# power.net
KiCad netlist of a schematic drawn in EAGLE
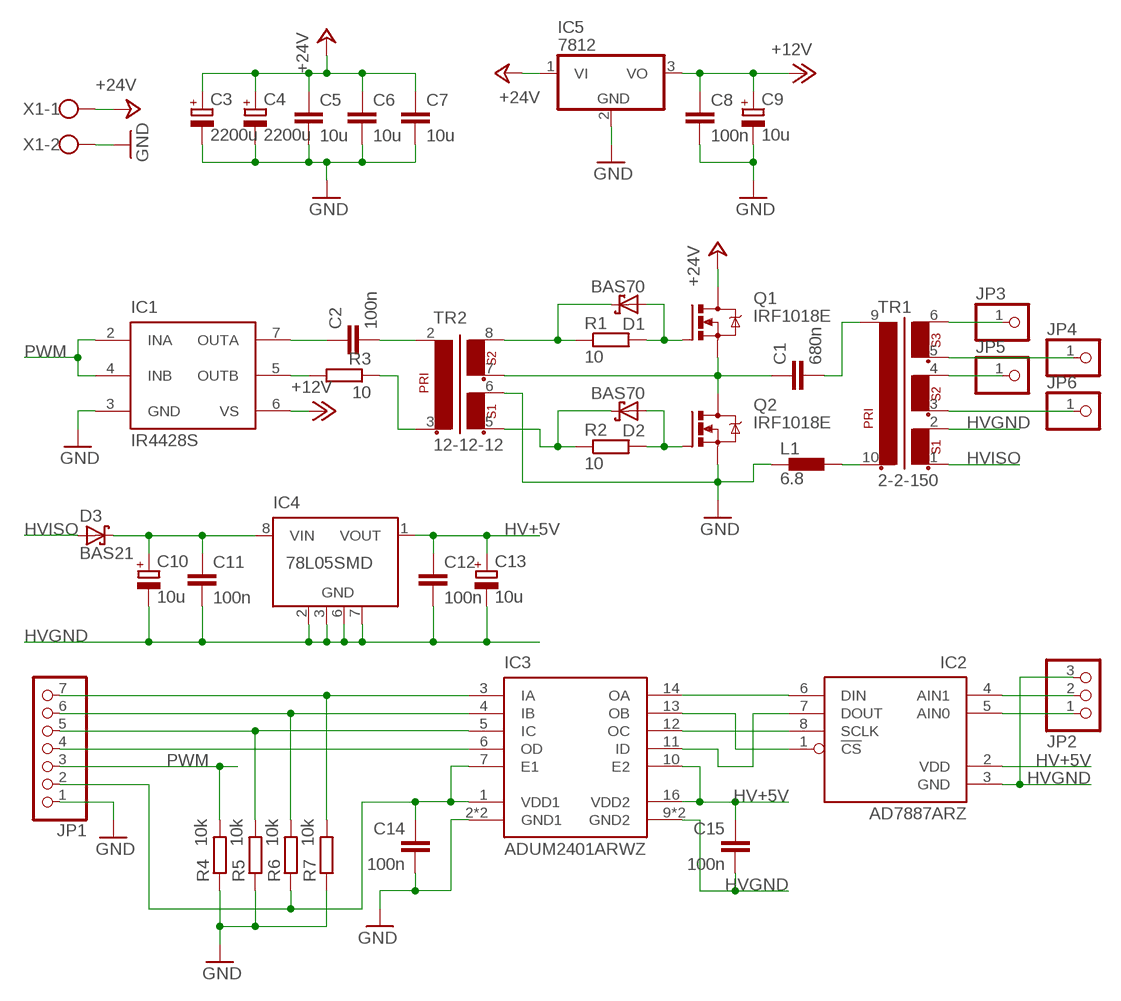
[diagram p0: schematic, sheet 1]

(export (version "E")
  (design (tool "Eeschema 10.0.6"))
  (components
    (comp (ref "C1")
      (value "680n")
      (footprint "eagle-import:C150-084X183")
      (libsource (lib "eagle-import") (part "C-EU150-084X183"))
    )
    (comp (ref "C2")
      (value "100n")
      (footprint "eagle-import:C1206")
      (libsource (lib "eagle-import") (part "C-EUC1206"))
    )
    (comp (ref "C3")
      (value "2200u")
      (footprint "eagle-import:E7,5-16")
      (libsource (lib "eagle-import") (part "CPOL-EUE7.5-16"))
    )
    (comp (ref "C4")
      (value "2200u")
      (footprint "eagle-import:E7,5-16")
      (libsource (lib "eagle-import") (part "CPOL-EUE7.5-16"))
    )
    (comp (ref "C5")
      (value "10u")
      (footprint "eagle-import:C1210")
      (libsource (lib "eagle-import") (part "C-EUC1210"))
    )
    (comp (ref "C6")
      (value "10u")
      (footprint "eagle-import:C1210")
      (libsource (lib "eagle-import") (part "C-EUC1210"))
    )
    (comp (ref "C7")
      (value "10u")
      (footprint "eagle-import:C1210")
      (libsource (lib "eagle-import") (part "C-EUC1210"))
    )
    (comp (ref "C8")
      (value "100n")
      (footprint "eagle-import:C1206")
      (libsource (lib "eagle-import") (part "C-EUC1206"))
    )
    (comp (ref "C9")
      (value "10u")
      (footprint "eagle-import:B_3528-21R")
      (libsource (lib "eagle-import") (part "CPOL-EUB/3528-21R"))
    )
    (comp (ref "C10")
      (value "10u")
      (footprint "eagle-import:B_3528-21R")
      (libsource (lib "eagle-import") (part "CPOL-EUB/3528-21R"))
    )
    (comp (ref "C11")
      (value "100n")
      (footprint "eagle-import:C1206")
      (libsource (lib "eagle-import") (part "C-EUC1206"))
    )
    (comp (ref "C12")
      (value "100n")
      (footprint "eagle-import:C1206")
      (libsource (lib "eagle-import") (part "C-EUC1206"))
    )
    (comp (ref "C13")
      (value "10u")
      (footprint "eagle-import:B_3528-21R")
      (libsource (lib "eagle-import") (part "CPOL-EUB/3528-21R"))
    )
    (comp (ref "C14")
      (value "100n")
      (footprint "eagle-import:C1206")
      (libsource (lib "eagle-import") (part "C-EUC1206"))
    )
    (comp (ref "C15")
      (value "100n")
      (footprint "eagle-import:C1206")
      (libsource (lib "eagle-import") (part "C-EUC1206"))
    )
    (comp (ref "D1")
      (value "BAS70")
      (footprint "eagle-import:SOT23")
      (libsource (lib "eagle-import") (part "BAS70"))
    )
    (comp (ref "D2")
      (value "BAS70")
      (footprint "eagle-import:SOT23")
      (libsource (lib "eagle-import") (part "BAS70"))
    )
    (comp (ref "D3")
      (value "BAS21")
      (footprint "eagle-import:SOT23")
      (libsource (lib "eagle-import") (part "BAS70"))
    )
    (comp (ref "IC1")
      (value "IR4428S")
      (footprint "eagle-import:SO08")
      (libsource (lib "eagle-import") (part "IR442S8"))
    )
    (comp (ref "IC2")
      (value "AD7887ARZ")
      (footprint "eagle-import:SO08")
      (libsource (lib "eagle-import") (part "AD7887ARZ"))
    )
    (comp (ref "IC3")
      (value "ADUM2401ARWZ")
      (footprint "eagle-import:SO-16W")
      (libsource (lib "eagle-import") (part "ADUM2401RWZA"))
    )
    (comp (ref "IC4")
      (value "78L05SMD")
      (footprint "eagle-import:SO08")
      (libsource (lib "eagle-import") (part "78LSMD05"))
    )
    (comp (ref "IC5")
      (value "7812")
      (footprint "eagle-import:D2PACK")
      (libsource (lib "eagle-import") (part "7812"))
    )
    (comp (ref "JP1")
      (value "PINHD-1X7/90")
      (footprint "eagle-import:1X07_90")
      (libsource (lib "eagle-import") (part "PINHD-1X7/90"))
    )
    (comp (ref "JP2")
      (value "PINHD-1X3/90")
      (footprint "eagle-import:1X03_90")
      (libsource (lib "eagle-import") (part "PINHD-1X3/90"))
    )
    (comp (ref "JP3")
      (value "PINHD-1X1")
      (footprint "eagle-import:1X01")
      (libsource (lib "eagle-import") (part "PINHD-1X1"))
    )
    (comp (ref "JP4")
      (value "PINHD-1X1")
      (footprint "eagle-import:1X01")
      (libsource (lib "eagle-import") (part "PINHD-1X1"))
    )
    (comp (ref "JP5")
      (value "PINHD-1X1")
      (footprint "eagle-import:1X01")
      (libsource (lib "eagle-import") (part "PINHD-1X1"))
    )
    (comp (ref "JP6")
      (value "PINHD-1X1")
      (footprint "eagle-import:1X01")
      (libsource (lib "eagle-import") (part "PINHD-1X1"))
    )
    (comp (ref "L1")
      (value "6.8")
      (footprint "eagle-import:TSL1112")
      (libsource (lib "eagle-import") (part "TSL1112"))
    )
    (comp (ref "Q1")
      (value "IRF1018E")
      (footprint "eagle-import:TO220BV")
      (libsource (lib "eagle-import") (part "IRF1018E"))
    )
    (comp (ref "Q2")
      (value "IRF1018E")
      (footprint "eagle-import:TO220BV")
      (libsource (lib "eagle-import") (part "IRF1018E"))
    )
    (comp (ref "R1")
      (value "10")
      (footprint "eagle-import:R0805")
      (libsource (lib "eagle-import") (part "R-EU_R0805"))
    )
    (comp (ref "R2")
      (value "10")
      (footprint "eagle-import:R0805")
      (libsource (lib "eagle-import") (part "R-EU_R0805"))
    )
    (comp (ref "R3")
      (value "10")
      (footprint "eagle-import:R0805")
      (libsource (lib "eagle-import") (part "R-EU_R0805"))
    )
    (comp (ref "R4")
      (value "10k")
      (footprint "eagle-import:R0805")
      (libsource (lib "eagle-import") (part "R-EU_R0805"))
    )
    (comp (ref "R5")
      (value "10k")
      (footprint "eagle-import:R0805")
      (libsource (lib "eagle-import") (part "R-EU_R0805"))
    )
    (comp (ref "R6")
      (value "10k")
      (footprint "eagle-import:R0805")
      (libsource (lib "eagle-import") (part "R-EU_R0805"))
    )
    (comp (ref "R7")
      (value "10k")
      (footprint "eagle-import:R0805")
      (libsource (lib "eagle-import") (part "R-EU_R0805"))
    )
    (comp (ref "TR1")
      (value "2-2-150")
      (footprint "eagle-import:RM12T1")
      (libsource (lib "eagle-import") (part "2-2-150"))
    )
    (comp (ref "TR2")
      (value "12-12-12")
      (footprint "eagle-import:RM5LS")
      (libsource (lib "eagle-import") (part "12-12-12"))
    )
    (comp (ref "X1")
      (value "W237-102")
      (footprint "eagle-import:W237-102")
      (fields (field (name "MPN") "237-102"))
      (libsource (lib "eagle-import") (part "W237-102"))
    )
  )
  (nets
    (net (code "1") (name "+12V") (class "Default")
      (node (ref "C8") (pin "1") (pinfunction "1_1") (pintype "passive"))
      (node (ref "C9") (pin "+") (pinfunction "+_+") (pintype "passive"))
      (node (ref "IC1") (pin "6") (pinfunction "VS_6") (pintype "power_in"))
      (node (ref "IC5") (pin "3") (pinfunction "VO_3") (pintype "passive"))
    )
    (net (code "2") (name "+24V") (class "Default")
      (node (ref "C3") (pin "+") (pinfunction "+_+") (pintype "passive"))
      (node (ref "C4") (pin "+") (pinfunction "+_+") (pintype "passive"))
      (node (ref "C5") (pin "1") (pinfunction "1_1") (pintype "passive"))
      (node (ref "C6") (pin "1") (pinfunction "1_1") (pintype "passive"))
      (node (ref "C7") (pin "1") (pinfunction "1_1") (pintype "passive"))
      (node (ref "IC5") (pin "1") (pinfunction "VI_1") (pintype "input"))
      (node (ref "Q1") (pin "D") (pinfunction "D_D") (pintype "passive"))
      (node (ref "X1") (pin "1") (pinfunction "KL_1") (pintype "passive"))
    )
    (net (code "3") (name "/HV+5V") (class "Default")
      (node (ref "C12") (pin "1") (pinfunction "1_1") (pintype "passive"))
      (node (ref "C13") (pin "+") (pinfunction "+_+") (pintype "passive"))
      (node (ref "C15") (pin "1") (pinfunction "1_1") (pintype "passive"))
      (node (ref "IC2") (pin "2") (pinfunction "VDD_2") (pintype "power_in"))
      (node (ref "IC3") (pin "10") (pinfunction "E2_10") (pintype "input"))
      (node (ref "IC3") (pin "16") (pinfunction "VDD2_16") (pintype "power_in"))
      (node (ref "IC4") (pin "1") (pinfunction "VOUT_1") (pintype "output"))
    )
    (net (code "4") (name "/HVGND") (class "Default")
      (node (ref "C10") (pin "-") (pinfunction "-_-") (pintype "passive"))
      (node (ref "C11") (pin "2") (pinfunction "2_2") (pintype "passive"))
      (node (ref "C12") (pin "2") (pinfunction "2_2") (pintype "passive"))
      (node (ref "C13") (pin "-") (pinfunction "-_-") (pintype "passive"))
      (node (ref "C15") (pin "2") (pinfunction "2_2") (pintype "passive"))
      (node (ref "IC2") (pin "3") (pinfunction "GND_3") (pintype "power_in"))
      (node (ref "IC3") (pin "15") (pinfunction "GND2_15") (pintype "power_in"))
      (node (ref "IC3") (pin "9") (pinfunction "GND2_9") (pintype "power_in"))
      (node (ref "IC4") (pin "2") (pinfunction "GND_2") (pintype "power_in"))
      (node (ref "IC4") (pin "3") (pinfunction "GND_3") (pintype "power_in"))
      (node (ref "IC4") (pin "6") (pinfunction "GND_6") (pintype "power_in"))
      (node (ref "IC4") (pin "7") (pinfunction "GND_7") (pintype "power_in"))
      (node (ref "JP2") (pin "3") (pinfunction "3_3") (pintype "passive"))
      (node (ref "TR1") (pin "2") (pinfunction "4_2") (pintype "passive"))
    )
    (net (code "5") (name "/HVISO") (class "Default")
      (node (ref "D3") (pin "1") (pinfunction "A_1") (pintype "passive"))
      (node (ref "TR1") (pin "1") (pinfunction "3_1") (pintype "passive"))
    )
    (net (code "6") (name "/PWM") (class "Default")
      (node (ref "IC1") (pin "2") (pinfunction "INA_2") (pintype "input"))
      (node (ref "IC1") (pin "4") (pinfunction "INB_4") (pintype "input"))
      (node (ref "JP1") (pin "3") (pinfunction "3_3") (pintype "passive"))
      (node (ref "R4") (pin "2") (pinfunction "2_2") (pintype "passive"))
    )
    (net (code "7") (name "GND") (class "Default")
      (node (ref "C14") (pin "2") (pinfunction "2_2") (pintype "passive"))
      (node (ref "C3") (pin "-") (pinfunction "-_-") (pintype "passive"))
      (node (ref "C4") (pin "-") (pinfunction "-_-") (pintype "passive"))
      (node (ref "C5") (pin "2") (pinfunction "2_2") (pintype "passive"))
      (node (ref "C6") (pin "2") (pinfunction "2_2") (pintype "passive"))
      (node (ref "C7") (pin "2") (pinfunction "2_2") (pintype "passive"))
      (node (ref "C8") (pin "2") (pinfunction "2_2") (pintype "passive"))
      (node (ref "C9") (pin "-") (pinfunction "-_-") (pintype "passive"))
      (node (ref "IC1") (pin "3") (pinfunction "GND_3") (pintype "power_in"))
      (node (ref "IC3") (pin "2") (pinfunction "GND1_2") (pintype "power_in"))
      (node (ref "IC3") (pin "8") (pinfunction "GND1_8") (pintype "power_in"))
      (node (ref "IC5") (pin "2") (pinfunction "GND_2") (pintype "passive"))
      (node (ref "JP1") (pin "1") (pinfunction "1_1") (pintype "passive"))
      (node (ref "L1") (pin "P$1") (pinfunction "1_P$1") (pintype "passive"))
      (node (ref "Q2") (pin "S") (pinfunction "S_S") (pintype "passive"))
      (node (ref "R4") (pin "1") (pinfunction "1_1") (pintype "passive"))
      (node (ref "R5") (pin "1") (pinfunction "1_1") (pintype "passive"))
      (node (ref "R7") (pin "1") (pinfunction "1_1") (pintype "passive"))
      (node (ref "TR2") (pin "6") (pinfunction "4_6") (pintype "passive"))
      (node (ref "X1") (pin "2") (pinfunction "KL_2") (pintype "passive"))
    )
    (net (code "8") (name "Net-(D1-A)") (class "Default")
      (node (ref "D1") (pin "1") (pinfunction "A_1") (pintype "passive"))
      (node (ref "Q1") (pin "G") (pinfunction "G_G") (pintype "passive"))
      (node (ref "R1") (pin "2") (pinfunction "2_2") (pintype "passive"))
    )
    (net (code "9") (name "Net-(D1-C)") (class "Default")
      (node (ref "D1") (pin "3") (pinfunction "C_3") (pintype "passive"))
      (node (ref "R1") (pin "1") (pinfunction "1_1") (pintype "passive"))
      (node (ref "TR2") (pin "8") (pinfunction "6_8") (pintype "passive"))
    )
    (net (code "10") (name "Net-(D2-A)") (class "Default")
      (node (ref "D2") (pin "1") (pinfunction "A_1") (pintype "passive"))
      (node (ref "Q2") (pin "G") (pinfunction "G_G") (pintype "passive"))
      (node (ref "R2") (pin "2") (pinfunction "2_2") (pintype "passive"))
    )
    (net (code "11") (name "Net-(D2-C)") (class "Default")
      (node (ref "D2") (pin "3") (pinfunction "C_3") (pintype "passive"))
      (node (ref "R2") (pin "1") (pinfunction "1_1") (pintype "passive"))
      (node (ref "TR2") (pin "5") (pinfunction "3_5") (pintype "passive"))
    )
    (net (code "12") (name "Net-(D3-C)") (class "Default")
      (node (ref "C10") (pin "+") (pinfunction "+_+") (pintype "passive"))
      (node (ref "C11") (pin "1") (pinfunction "1_1") (pintype "passive"))
      (node (ref "D3") (pin "3") (pinfunction "C_3") (pintype "passive"))
      (node (ref "IC4") (pin "8") (pinfunction "VIN_8") (pintype "passive"))
    )
    (net (code "13") (name "Net-(IC1-OUTA)") (class "Default")
      (node (ref "C2") (pin "1") (pinfunction "1_1") (pintype "passive"))
      (node (ref "IC1") (pin "7") (pinfunction "OUTA_7") (pintype "output"))
    )
    (net (code "14") (name "Net-(IC1-OUTB)") (class "Default")
      (node (ref "IC1") (pin "5") (pinfunction "OUTB_5") (pintype "output"))
      (node (ref "R3") (pin "2") (pinfunction "2_2") (pintype "passive"))
    )
    (net (code "15") (name "Net-(IC2-AIN0)") (class "Default")
      (node (ref "IC2") (pin "5") (pinfunction "AIN0_5") (pintype "input"))
      (node (ref "JP2") (pin "1") (pinfunction "1_1") (pintype "passive"))
    )
    (net (code "16") (name "Net-(IC2-AIN1)") (class "Default")
      (node (ref "IC2") (pin "4") (pinfunction "AIN1_4") (pintype "input"))
      (node (ref "JP2") (pin "2") (pinfunction "2_2") (pintype "passive"))
    )
    (net (code "17") (name "Net-(IC2-DIN)") (class "Default")
      (node (ref "IC2") (pin "6") (pinfunction "DIN_6") (pintype "input"))
      (node (ref "IC3") (pin "14") (pinfunction "OA_14") (pintype "output"))
    )
    (net (code "18") (name "Net-(IC2-DOUT)") (class "Default")
      (node (ref "IC2") (pin "7") (pinfunction "DOUT_7") (pintype "output"))
      (node (ref "IC3") (pin "11") (pinfunction "ID_11") (pintype "input"))
    )
    (net (code "19") (name "Net-(IC2-SCLK)") (class "Default")
      (node (ref "IC2") (pin "8") (pinfunction "SCLK_8") (pintype "input"))
      (node (ref "IC3") (pin "12") (pinfunction "OC_12") (pintype "output"))
    )
    (net (code "20") (name "Net-(IC2-~{CS})") (class "Default")
      (node (ref "IC2") (pin "1") (pinfunction "~{CS}_1") (pintype "input"))
      (node (ref "IC3") (pin "13") (pinfunction "OB_13") (pintype "output"))
    )
    (net (code "21") (name "Net-(IC3-E1)") (class "Default")
      (node (ref "C14") (pin "1") (pinfunction "1_1") (pintype "passive"))
      (node (ref "IC3") (pin "1") (pinfunction "VDD1_1") (pintype "power_in"))
      (node (ref "IC3") (pin "7") (pinfunction "E1_7") (pintype "input"))
      (node (ref "JP1") (pin "2") (pinfunction "2_2") (pintype "passive"))
      (node (ref "R6") (pin "1") (pinfunction "1_1") (pintype "passive"))
    )
    (net (code "22") (name "Net-(IC3-IA)") (class "Default")
      (node (ref "IC3") (pin "3") (pinfunction "IA_3") (pintype "input"))
      (node (ref "JP1") (pin "7") (pinfunction "7_7") (pintype "passive"))
      (node (ref "R7") (pin "2") (pinfunction "2_2") (pintype "passive"))
    )
    (net (code "23") (name "Net-(IC3-IB)") (class "Default")
      (node (ref "IC3") (pin "4") (pinfunction "IB_4") (pintype "input"))
      (node (ref "JP1") (pin "6") (pinfunction "6_6") (pintype "passive"))
      (node (ref "R6") (pin "2") (pinfunction "2_2") (pintype "passive"))
    )
    (net (code "24") (name "Net-(IC3-IC)") (class "Default")
      (node (ref "IC3") (pin "5") (pinfunction "IC_5") (pintype "input"))
      (node (ref "JP1") (pin "5") (pinfunction "5_5") (pintype "passive"))
      (node (ref "R5") (pin "2") (pinfunction "2_2") (pintype "passive"))
    )
    (net (code "25") (name "Net-(IC3-OD)") (class "Default")
      (node (ref "IC3") (pin "6") (pinfunction "OD_6") (pintype "output"))
      (node (ref "JP1") (pin "4") (pinfunction "4_4") (pintype "passive"))
    )
    (net (code "26") (name "Net-(L1-2)") (class "Default")
      (node (ref "L1") (pin "P$2") (pinfunction "2_P$2") (pintype "passive"))
      (node (ref "TR1") (pin "10") (pinfunction "2_10") (pintype "passive"))
    )
    (net (code "27") (name "Net-(TR1-1)") (class "Default")
      (node (ref "C1") (pin "2") (pinfunction "2_2") (pintype "passive"))
      (node (ref "TR1") (pin "9") (pinfunction "1_9") (pintype "passive"))
    )
    (net (code "28") (name "Net-(TR1-5)") (class "Default")
      (node (ref "JP6") (pin "1") (pinfunction "1_1") (pintype "passive"))
      (node (ref "TR1") (pin "3") (pinfunction "5_3") (pintype "passive"))
    )
    (net (code "29") (name "Net-(TR1-6)") (class "Default")
      (node (ref "JP5") (pin "1") (pinfunction "1_1") (pintype "passive"))
      (node (ref "TR1") (pin "4") (pinfunction "6_4") (pintype "passive"))
    )
    (net (code "30") (name "Net-(TR1-7)") (class "Default")
      (node (ref "JP4") (pin "1") (pinfunction "1_1") (pintype "passive"))
      (node (ref "TR1") (pin "5") (pinfunction "7_5") (pintype "passive"))
    )
    (net (code "31") (name "Net-(TR1-8)") (class "Default")
      (node (ref "JP3") (pin "1") (pinfunction "1_1") (pintype "passive"))
      (node (ref "TR1") (pin "6") (pinfunction "8_6") (pintype "passive"))
    )
    (net (code "32") (name "Net-(TR2-1)") (class "Default")
      (node (ref "C2") (pin "2") (pinfunction "2_2") (pintype "passive"))
      (node (ref "TR2") (pin "2") (pinfunction "1_2") (pintype "passive"))
    )
    (net (code "33") (name "Net-(TR2-2)") (class "Default")
      (node (ref "R3") (pin "1") (pinfunction "1_1") (pintype "passive"))
      (node (ref "TR2") (pin "3") (pinfunction "2_3") (pintype "passive"))
    )
    (net (code "34") (name "Net-(TR2-5)") (class "Default")
      (node (ref "C1") (pin "1") (pinfunction "1_1") (pintype "passive"))
      (node (ref "Q1") (pin "S") (pinfunction "S_S") (pintype "passive"))
      (node (ref "Q2") (pin "D") (pinfunction "D_D") (pintype "passive"))
      (node (ref "TR2") (pin "7") (pinfunction "5_7") (pintype "passive"))
    )
  )
)
